# rocket_pack-pad.net
KiCad netlist of a schematic drawn in EAGLE
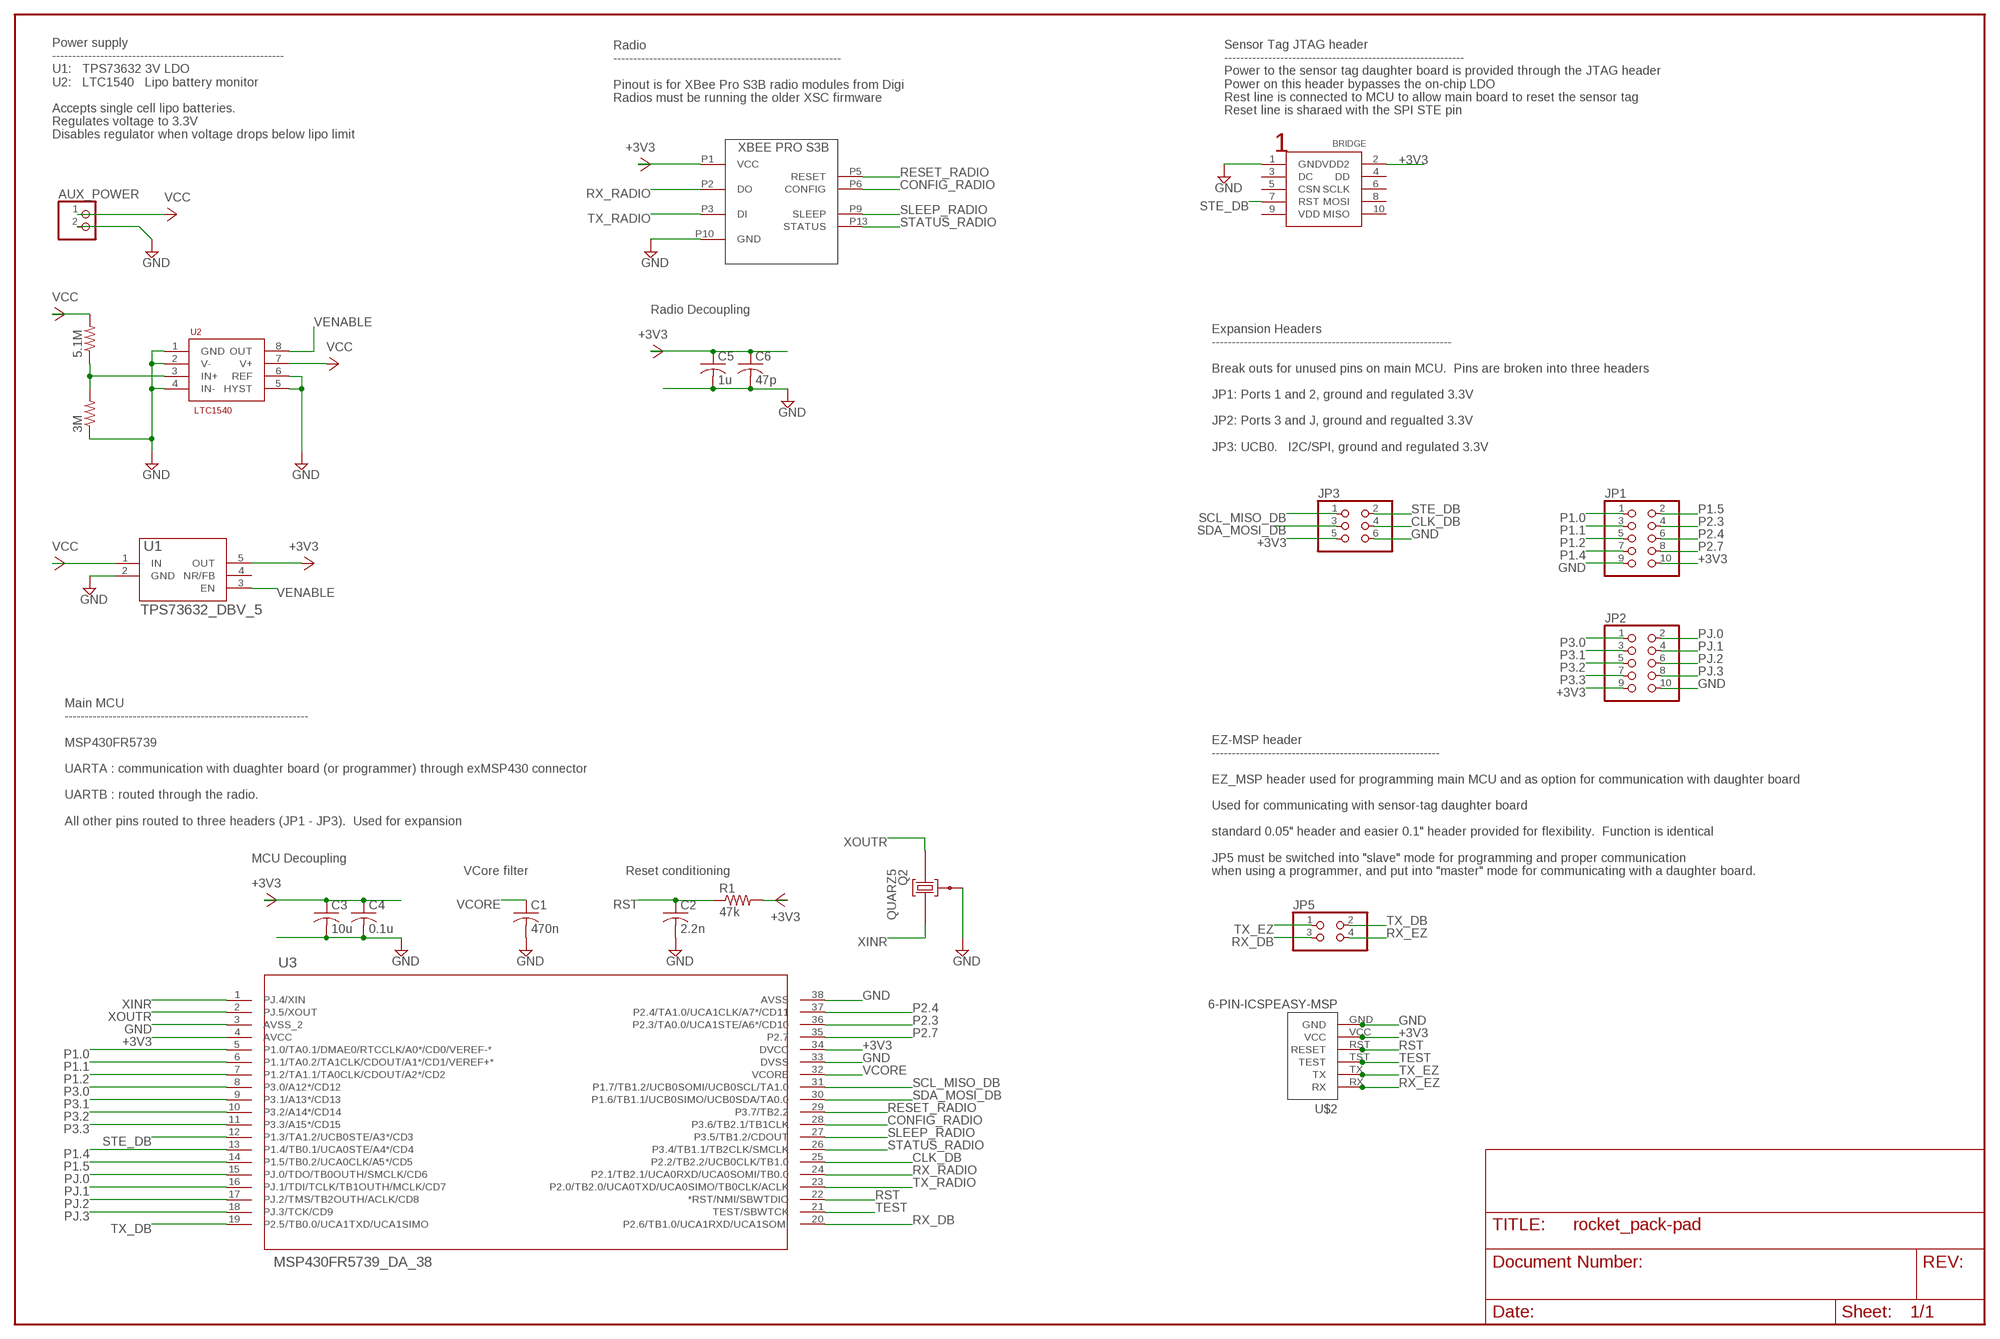
[diagram p0: schematic, sheet 1]

(export (version "E")
  (design (tool "Eeschema 10.0.6"))
  (components
    (comp (ref "3M")
      (value "R-US_R1206")
      (footprint "eagle-import:R1206")
      (libsource (lib "eagle-import") (part "R-US_R1206"))
    )
    (comp (ref "5.1M")
      (value "R-US_R1206")
      (footprint "eagle-import:R1206")
      (libsource (lib "eagle-import") (part "R-US_R1206"))
    )
    (comp (ref "AUX_POWER")
      (value "PINHD-1X2")
      (footprint "eagle-import:1X02")
      (libsource (lib "eagle-import") (part "PINHD-1X2"))
    )
    (comp (ref "BRIDGE")
      (value "CC-DEBUG")
      (footprint "eagle-import:2X5-1.27MM")
      (libsource (lib "eagle-import") (part "CC-DEBUG"))
    )
    (comp (ref "C1")
      (value "470n")
      (footprint "eagle-import:C1206")
      (libsource (lib "eagle-import") (part "C-USC1206"))
    )
    (comp (ref "C2")
      (value "2.2n")
      (footprint "eagle-import:C1206")
      (libsource (lib "eagle-import") (part "C-USC1206"))
    )
    (comp (ref "C3")
      (value "10u")
      (footprint "eagle-import:C1206")
      (libsource (lib "eagle-import") (part "C-USC1206"))
    )
    (comp (ref "C4")
      (value "0.1u")
      (footprint "eagle-import:C1206")
      (libsource (lib "eagle-import") (part "C-USC1206"))
    )
    (comp (ref "C5")
      (value "1u")
      (footprint "eagle-import:C1206")
      (libsource (lib "eagle-import") (part "C-USC1206"))
    )
    (comp (ref "C6")
      (value "47p")
      (footprint "eagle-import:C1206")
      (libsource (lib "eagle-import") (part "C-USC1206"))
    )
    (comp (ref "JP1")
      (value "PINHD-2X5")
      (footprint "eagle-import:2X05")
      (libsource (lib "eagle-import") (part "PINHD-2X5"))
    )
    (comp (ref "JP2")
      (value "PINHD-2X5")
      (footprint "eagle-import:2X05")
      (libsource (lib "eagle-import") (part "PINHD-2X5"))
    )
    (comp (ref "JP3")
      (value "PINHD-2X3")
      (footprint "eagle-import:2X03")
      (libsource (lib "eagle-import") (part "PINHD-2X3"))
    )
    (comp (ref "JP5")
      (value "PINHD-2X2")
      (footprint "eagle-import:2X02")
      (libsource (lib "eagle-import") (part "PINHD-2X2"))
    )
    (comp (ref "Q2")
      (value "QUARZ5")
      (footprint "eagle-import:QUARZ5")
      (libsource (lib "eagle-import") (part "QUARZ5"))
    )
    (comp (ref "R1")
      (value "47k")
      (footprint "eagle-import:R1206")
      (libsource (lib "eagle-import") (part "R-US_R1206"))
    )
    (comp (ref "U$1")
      (value "XBEE_PRO_S3B")
      (footprint "eagle-import:PRO_S3B")
      (libsource (lib "eagle-import") (part "XBEE_PRO_S3B"))
    )
    (comp (ref "U$2")
      (value "6-PIN-ICSPEASY-MSP")
      (footprint "eagle-import:EASYMSP-6PIN")
      (libsource (lib "eagle-import") (part "6-PIN-ICSPEASY-MSP"))
    )
    (comp (ref "U1")
      (value "TPS73632_DBV_5")
      (footprint "eagle-import:DBV5")
      (fields
        (field (name "GENERIC_PART_NUMBER") "TPS73632")
        (field (name "MANUFACTURER") "Texas Instruments")
        (field (name "MANUFACTURER_PART_NUMBER") "tps73632_dbv_5")
      )
      (libsource (lib "eagle-import") (part "TPS73632_DBV_5"))
    )
    (comp (ref "U2")
      (value "LTC1540")
      (footprint "eagle-import:S8")
      (libsource (lib "eagle-import") (part "LTC1540"))
    )
    (comp (ref "U3")
      (value "MSP430FR5739_DA_38")
      (footprint "eagle-import:DA38")
      (fields
        (field (name "GENERIC_PART_NUMBER") "MSP430FR5739")
        (field (name "MANUFACTURER") "Texas Instruments")
        (field (name "MANUFACTURER_PART_NUMBER") "msp430fr5739_da_38")
      )
      (libsource (lib "eagle-import") (part "MSP430FR5739_DA_38"))
    )
  )
  (nets
    (net (code "1") (name "+3V3") (class "Default")
      (node (ref "BRIDGE") (pin "2") (pinfunction "VDD2_2") (pintype "bidirectional"))
      (node (ref "C3") (pin "1") (pinfunction "1_1") (pintype "passive"))
      (node (ref "C4") (pin "1") (pinfunction "1_1") (pintype "passive"))
      (node (ref "C5") (pin "1") (pinfunction "1_1") (pintype "passive"))
      (node (ref "C6") (pin "1") (pinfunction "1_1") (pintype "passive"))
      (node (ref "JP1") (pin "10") (pinfunction "10_10") (pintype "passive"))
      (node (ref "JP2") (pin "9") (pinfunction "9_9") (pintype "passive"))
      (node (ref "JP3") (pin "5") (pinfunction "5_5") (pintype "passive"))
      (node (ref "R1") (pin "2") (pinfunction "2_2") (pintype "passive"))
      (node (ref "U$1") (pin "P1") (pinfunction "VCC_P1") (pintype "bidirectional"))
      (node (ref "U$2") (pin "VCC") (pinfunction "VCC_VCC") (pintype "bidirectional"))
      (node (ref "U1") (pin "5") (pinfunction "OUT_5") (pintype "output"))
      (node (ref "U3") (pin "34") (pinfunction "DVCC_34") (pintype "power_in"))
      (node (ref "U3") (pin "4") (pinfunction "AVCC_4") (pintype "power_in"))
    )
    (net (code "2") (name "/CLK_DB") (class "Default")
      (node (ref "JP3") (pin "4") (pinfunction "4_4") (pintype "passive"))
      (node (ref "U3") (pin "25") (pinfunction "P2.2/TB2.2/UCB0CLK/TB1.0_25") (pintype "bidirectional"))
    )
    (net (code "3") (name "/CONFIG_RADIO") (class "Default")
      (node (ref "U$1") (pin "P6") (pinfunction "CONFIG_P6") (pintype "bidirectional"))
      (node (ref "U3") (pin "28") (pinfunction "P3.6/TB2.1/TB1CLK_28") (pintype "bidirectional"))
    )
    (net (code "4") (name "/P1.0") (class "Default")
      (node (ref "JP1") (pin "1") (pinfunction "1_1") (pintype "passive"))
      (node (ref "U3") (pin "5") (pinfunction "P1.0/TA0.1/DMAE0/RTCCLK/A0*/CD0/VEREF-*_5") (pintype "bidirectional"))
    )
    (net (code "5") (name "/P1.1") (class "Default")
      (node (ref "JP1") (pin "3") (pinfunction "3_3") (pintype "passive"))
      (node (ref "U3") (pin "6") (pinfunction "P1.1/TA0.2/TA1CLK/CDOUT/A1*/CD1/VEREF+*_6") (pintype "bidirectional"))
    )
    (net (code "6") (name "/P1.2") (class "Default")
      (node (ref "JP1") (pin "5") (pinfunction "5_5") (pintype "passive"))
      (node (ref "U3") (pin "7") (pinfunction "P1.2/TA1.1/TA0CLK/CDOUT/A2*/CD2_7") (pintype "bidirectional"))
    )
    (net (code "7") (name "/P1.4") (class "Default")
      (node (ref "JP1") (pin "7") (pinfunction "7_7") (pintype "passive"))
      (node (ref "U3") (pin "13") (pinfunction "P1.4/TB0.1/UCA0STE/A4*/CD4_13") (pintype "bidirectional"))
    )
    (net (code "8") (name "/P1.5") (class "Default")
      (node (ref "JP1") (pin "2") (pinfunction "2_2") (pintype "passive"))
      (node (ref "U3") (pin "14") (pinfunction "P1.5/TB0.2/UCA0CLK/A5*/CD5_14") (pintype "bidirectional"))
    )
    (net (code "9") (name "/P2.3") (class "Default")
      (node (ref "JP1") (pin "4") (pinfunction "4_4") (pintype "passive"))
      (node (ref "U3") (pin "36") (pinfunction "P2.3/TA0.0/UCA1STE/A6*/CD10_36") (pintype "bidirectional"))
    )
    (net (code "10") (name "/P2.4") (class "Default")
      (node (ref "JP1") (pin "6") (pinfunction "6_6") (pintype "passive"))
      (node (ref "U3") (pin "37") (pinfunction "P2.4/TA1.0/UCA1CLK/A7*/CD11_37") (pintype "bidirectional"))
    )
    (net (code "11") (name "/P2.7") (class "Default")
      (node (ref "JP1") (pin "8") (pinfunction "8_8") (pintype "passive"))
      (node (ref "U3") (pin "35") (pinfunction "P2.7_35") (pintype "bidirectional"))
    )
    (net (code "12") (name "/P3.0") (class "Default")
      (node (ref "JP2") (pin "1") (pinfunction "1_1") (pintype "passive"))
      (node (ref "U3") (pin "8") (pinfunction "P3.0/A12*/CD12_8") (pintype "bidirectional"))
    )
    (net (code "13") (name "/P3.1") (class "Default")
      (node (ref "JP2") (pin "3") (pinfunction "3_3") (pintype "passive"))
      (node (ref "U3") (pin "9") (pinfunction "P3.1/A13*/CD13_9") (pintype "bidirectional"))
    )
    (net (code "14") (name "/P3.2") (class "Default")
      (node (ref "JP2") (pin "5") (pinfunction "5_5") (pintype "passive"))
      (node (ref "U3") (pin "10") (pinfunction "P3.2/A14*/CD14_10") (pintype "bidirectional"))
    )
    (net (code "15") (name "/P3.3") (class "Default")
      (node (ref "JP2") (pin "7") (pinfunction "7_7") (pintype "passive"))
      (node (ref "U3") (pin "11") (pinfunction "P3.3/A15*/CD15_11") (pintype "bidirectional"))
    )
    (net (code "16") (name "/PJ.0") (class "Default")
      (node (ref "JP2") (pin "2") (pinfunction "2_2") (pintype "passive"))
      (node (ref "U3") (pin "15") (pinfunction "PJ.0/TDO/TB0OUTH/SMCLK/CD6_15") (pintype "bidirectional"))
    )
    (net (code "17") (name "/PJ.1") (class "Default")
      (node (ref "JP2") (pin "4") (pinfunction "4_4") (pintype "passive"))
      (node (ref "U3") (pin "16") (pinfunction "PJ.1/TDI/TCLK/TB1OUTH/MCLK/CD7_16") (pintype "bidirectional"))
    )
    (net (code "18") (name "/PJ.2") (class "Default")
      (node (ref "JP2") (pin "6") (pinfunction "6_6") (pintype "passive"))
      (node (ref "U3") (pin "17") (pinfunction "PJ.2/TMS/TB2OUTH/ACLK/CD8_17") (pintype "bidirectional"))
    )
    (net (code "19") (name "/PJ.3") (class "Default")
      (node (ref "JP2") (pin "8") (pinfunction "8_8") (pintype "passive"))
      (node (ref "U3") (pin "18") (pinfunction "PJ.3/TCK/CD9_18") (pintype "bidirectional"))
    )
    (net (code "20") (name "/RESET_RADIO") (class "Default")
      (node (ref "U$1") (pin "P5") (pinfunction "RESET_P5") (pintype "bidirectional"))
      (node (ref "U3") (pin "29") (pinfunction "P3.7/TB2.2_29") (pintype "bidirectional"))
    )
    (net (code "21") (name "/RST") (class "Default")
      (node (ref "C2") (pin "1") (pinfunction "1_1") (pintype "passive"))
      (node (ref "R1") (pin "1") (pinfunction "1_1") (pintype "passive"))
      (node (ref "U$2") (pin "RST") (pinfunction "RESET_RST") (pintype "bidirectional"))
      (node (ref "U3") (pin "22") (pinfunction "*RST/NMI/SBWTDIO_22") (pintype "bidirectional"))
    )
    (net (code "22") (name "/RX_DB") (class "Default")
      (node (ref "JP5") (pin "3") (pinfunction "3_3") (pintype "passive"))
      (node (ref "U3") (pin "20") (pinfunction "P2.6/TB1.0/UCA1RXD/UCA1SOMI_20") (pintype "bidirectional"))
    )
    (net (code "23") (name "/RX_EZ") (class "Default")
      (node (ref "JP5") (pin "4") (pinfunction "4_4") (pintype "passive"))
      (node (ref "U$2") (pin "RX") (pinfunction "RX_RX") (pintype "bidirectional"))
    )
    (net (code "24") (name "/RX_RADIO") (class "Default")
      (node (ref "U$1") (pin "P2") (pinfunction "DO_P2") (pintype "bidirectional"))
      (node (ref "U3") (pin "24") (pinfunction "P2.1/TB2.1/UCA0RXD/UCA0SOMI/TB0.0_24") (pintype "bidirectional"))
    )
    (net (code "25") (name "/SCL_MISO_DB") (class "Default")
      (node (ref "JP3") (pin "1") (pinfunction "1_1") (pintype "passive"))
      (node (ref "U3") (pin "31") (pinfunction "P1.7/TB1.2/UCB0SOMI/UCB0SCL/TA1.0_31") (pintype "bidirectional"))
    )
    (net (code "26") (name "/SDA_MOSI_DB") (class "Default")
      (node (ref "JP3") (pin "3") (pinfunction "3_3") (pintype "passive"))
      (node (ref "U3") (pin "30") (pinfunction "P1.6/TB1.1/UCB0SIMO/UCB0SDA/TA0.0_30") (pintype "bidirectional"))
    )
    (net (code "27") (name "/SLEEP_RADIO") (class "Default")
      (node (ref "U$1") (pin "P9") (pinfunction "SLEEP_P9") (pintype "bidirectional"))
      (node (ref "U3") (pin "27") (pinfunction "P3.5/TB1.2/CDOUT_27") (pintype "bidirectional"))
    )
    (net (code "28") (name "/STATUS_RADIO") (class "Default")
      (node (ref "U$1") (pin "P13") (pinfunction "STATUS_P13") (pintype "bidirectional"))
      (node (ref "U3") (pin "26") (pinfunction "P3.4/TB1.1/TB2CLK/SMCLK_26") (pintype "bidirectional"))
    )
    (net (code "29") (name "/STE_DB") (class "Default")
      (node (ref "BRIDGE") (pin "7") (pinfunction "RST_7") (pintype "bidirectional"))
      (node (ref "JP3") (pin "2") (pinfunction "2_2") (pintype "passive"))
      (node (ref "U3") (pin "12") (pinfunction "P1.3/TA1.2/UCB0STE/A3*/CD3_12") (pintype "bidirectional"))
    )
    (net (code "30") (name "/TEST") (class "Default")
      (node (ref "U$2") (pin "TST") (pinfunction "TEST_TST") (pintype "bidirectional"))
      (node (ref "U3") (pin "21") (pinfunction "TEST/SBWTCK_21") (pintype "bidirectional"))
    )
    (net (code "31") (name "/TX_DB") (class "Default")
      (node (ref "JP5") (pin "2") (pinfunction "2_2") (pintype "passive"))
      (node (ref "U3") (pin "19") (pinfunction "P2.5/TB0.0/UCA1TXD/UCA1SIMO_19") (pintype "bidirectional"))
    )
    (net (code "32") (name "/TX_EZ") (class "Default")
      (node (ref "JP5") (pin "1") (pinfunction "1_1") (pintype "passive"))
      (node (ref "U$2") (pin "TX") (pinfunction "TX_TX") (pintype "bidirectional"))
    )
    (net (code "33") (name "/TX_RADIO") (class "Default")
      (node (ref "U$1") (pin "P3") (pinfunction "DI_P3") (pintype "bidirectional"))
      (node (ref "U3") (pin "23") (pinfunction "P2.0/TB2.0/UCA0TXD/UCA0SIMO/TB0CLK/ACLK_23") (pintype "bidirectional"))
    )
    (net (code "34") (name "/VCORE") (class "Default")
      (node (ref "C1") (pin "1") (pinfunction "1_1") (pintype "passive"))
      (node (ref "U3") (pin "32") (pinfunction "VCORE_32") (pintype "power_in"))
    )
    (net (code "35") (name "/VENABLE") (class "Default")
      (node (ref "U1") (pin "3") (pinfunction "EN_3") (pintype "passive"))
      (node (ref "U2") (pin "8") (pinfunction "OUT_8") (pintype "bidirectional"))
    )
    (net (code "36") (name "/XINR") (class "Default")
      (node (ref "Q2") (pin "1") (pinfunction "1_1") (pintype "passive"))
      (node (ref "U3") (pin "1") (pinfunction "PJ.4/XIN_1") (pintype "bidirectional"))
    )
    (net (code "37") (name "/XOUTR") (class "Default")
      (node (ref "Q2") (pin "2") (pinfunction "2_2") (pintype "passive"))
      (node (ref "U3") (pin "2") (pinfunction "PJ.5/XOUT_2") (pintype "bidirectional"))
    )
    (net (code "38") (name "GND") (class "Default")
      (node (ref "3M") (pin "1") (pinfunction "1_1") (pintype "passive"))
      (node (ref "AUX_POWER") (pin "2") (pinfunction "2_2") (pintype "passive"))
      (node (ref "BRIDGE") (pin "1") (pinfunction "GND_1") (pintype "bidirectional"))
      (node (ref "C1") (pin "2") (pinfunction "2_2") (pintype "passive"))
      (node (ref "C2") (pin "2") (pinfunction "2_2") (pintype "passive"))
      (node (ref "C3") (pin "2") (pinfunction "2_2") (pintype "passive"))
      (node (ref "C4") (pin "2") (pinfunction "2_2") (pintype "passive"))
      (node (ref "C5") (pin "2") (pinfunction "2_2") (pintype "passive"))
      (node (ref "C6") (pin "2") (pinfunction "2_2") (pintype "passive"))
      (node (ref "JP1") (pin "9") (pinfunction "9_9") (pintype "passive"))
      (node (ref "JP2") (pin "10") (pinfunction "10_10") (pintype "passive"))
      (node (ref "JP3") (pin "6") (pinfunction "6_6") (pintype "passive"))
      (node (ref "Q2") (pin "GND@0") (pinfunction "0_GND@0") (pintype "passive"))
      (node (ref "U$1") (pin "P10") (pinfunction "GND_P10") (pintype "bidirectional"))
      (node (ref "U$2") (pin "GND") (pinfunction "GND_GND") (pintype "bidirectional"))
      (node (ref "U1") (pin "2") (pinfunction "GND_2") (pintype "power_in"))
      (node (ref "U2") (pin "1") (pinfunction "GND_1") (pintype "bidirectional"))
      (node (ref "U2") (pin "2") (pinfunction "V-_2") (pintype "bidirectional"))
      (node (ref "U2") (pin "4") (pinfunction "IN-_4") (pintype "bidirectional"))
      (node (ref "U2") (pin "5") (pinfunction "HYST_5") (pintype "bidirectional"))
      (node (ref "U2") (pin "6") (pinfunction "REF_6") (pintype "bidirectional"))
      (node (ref "U3") (pin "3") (pinfunction "AVSS_2_3") (pintype "power_in"))
      (node (ref "U3") (pin "33") (pinfunction "DVSS_33") (pintype "power_in"))
      (node (ref "U3") (pin "38") (pinfunction "AVSS_38") (pintype "power_in"))
    )
    (net (code "39") (name "Net-(U2-IN+)") (class "Default")
      (node (ref "3M") (pin "2") (pinfunction "2_2") (pintype "passive"))
      (node (ref "5.1M") (pin "1") (pinfunction "1_1") (pintype "passive"))
      (node (ref "U2") (pin "3") (pinfunction "IN+_3") (pintype "bidirectional"))
    )
    (net (code "40") (name "VCC") (class "Default")
      (node (ref "5.1M") (pin "2") (pinfunction "2_2") (pintype "passive"))
      (node (ref "AUX_POWER") (pin "1") (pinfunction "1_1") (pintype "passive"))
      (node (ref "U1") (pin "1") (pinfunction "IN_1") (pintype "input"))
      (node (ref "U2") (pin "7") (pinfunction "V+_7") (pintype "bidirectional"))
    )
    (net (code "41") (name "unconnected-(BRIDGE-CSN-Pad5)") (class "Default")
      (node (ref "BRIDGE") (pin "5") (pinfunction "CSN_5") (pintype "bidirectional"))
    )
    (net (code "42") (name "unconnected-(BRIDGE-DC-Pad3)") (class "Default")
      (node (ref "BRIDGE") (pin "3") (pinfunction "DC_3") (pintype "bidirectional"))
    )
    (net (code "43") (name "unconnected-(BRIDGE-DD-Pad4)") (class "Default")
      (node (ref "BRIDGE") (pin "4") (pinfunction "DD_4") (pintype "bidirectional"))
    )
    (net (code "44") (name "unconnected-(BRIDGE-MISO-Pad10)") (class "Default")
      (node (ref "BRIDGE") (pin "10") (pinfunction "MISO_10") (pintype "bidirectional"))
    )
    (net (code "45") (name "unconnected-(BRIDGE-MOSI-Pad8)") (class "Default")
      (node (ref "BRIDGE") (pin "8") (pinfunction "MOSI_8") (pintype "bidirectional"))
    )
    (net (code "46") (name "unconnected-(BRIDGE-SCLK-Pad6)") (class "Default")
      (node (ref "BRIDGE") (pin "6") (pinfunction "SCLK_6") (pintype "bidirectional"))
    )
    (net (code "47") (name "unconnected-(BRIDGE-VDD-Pad9)") (class "Default")
      (node (ref "BRIDGE") (pin "9") (pinfunction "VDD_9") (pintype "bidirectional"))
    )
    (net (code "48") (name "unconnected-(U1-NR{slash}FB-Pad4)") (class "Default")
      (node (ref "U1") (pin "4") (pinfunction "NR/FB_4") (pintype "bidirectional"))
    )
  )
)
